# Power_Supply_TLVM13630.net
KiCad netlist of a schematic drawn in Altium Designer
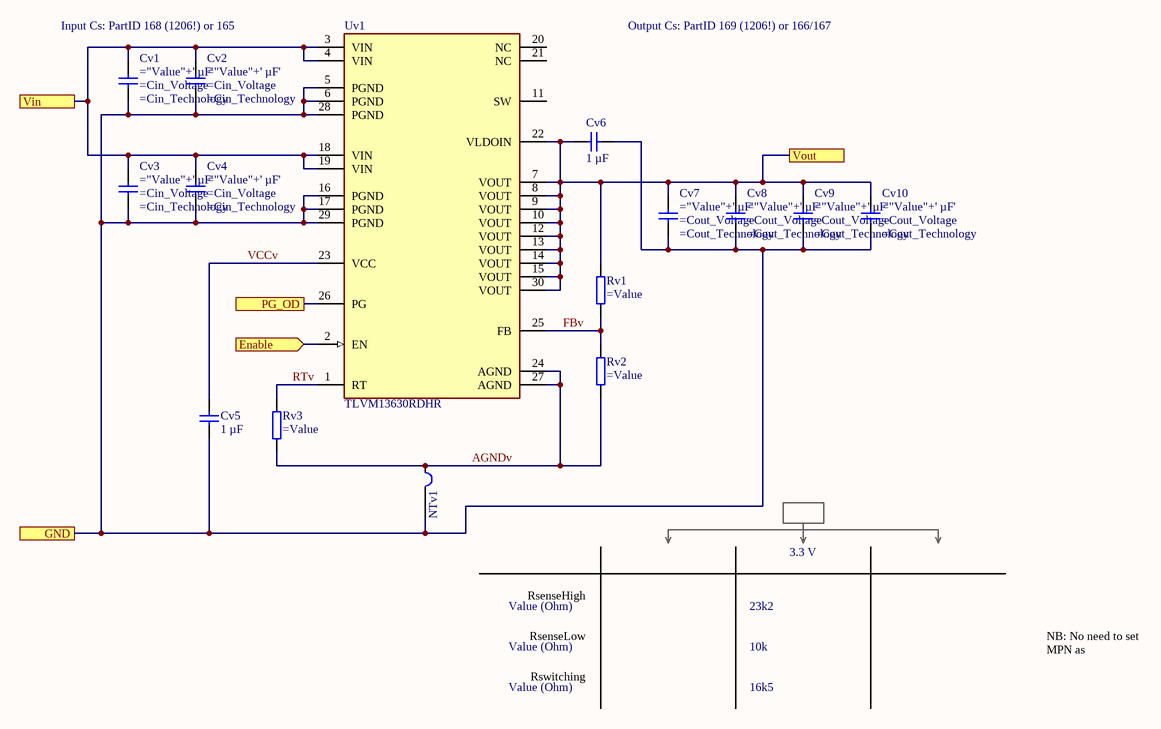
[diagram p0: Power_Supply_TLVM13630.SchDoc]

(export (version "E")
  (design (tool "Eeschema 10.0.6"))
  (components
    (comp (ref "Cv1")
      (value "µF")
      (footprint "C_1210_TE")
      (description "Generic capacitor (parametric)")
      (fields
        (field (name "MANUFACTURER PART NUMBER") "UZgen_C_1210_uF__")
        (field (name "MANUFACTURER") "UZgen")
        (field (name "CREATED FROM") "UZgenTool")
      )
      (libsource (lib "user") (part "CAP-NP"))
    )
    (comp (ref "Cv2")
      (value "µF")
      (footprint "C_1210_TE")
      (description "Generic capacitor (parametric)")
      (fields
        (field (name "MANUFACTURER PART NUMBER") "UZgen_C_1210_uF__")
        (field (name "MANUFACTURER") "UZgen")
        (field (name "CREATED FROM") "UZgenTool")
      )
      (libsource (lib "user") (part "CAP-NP"))
    )
    (comp (ref "Cv3")
      (value "µF")
      (footprint "C_1210_TE")
      (description "Generic capacitor (parametric)")
      (fields
        (field (name "MANUFACTURER PART NUMBER") "UZgen_C_1210_uF__")
        (field (name "MANUFACTURER") "UZgen")
        (field (name "CREATED FROM") "UZgenTool")
      )
      (libsource (lib "user") (part "CAP-NP"))
    )
    (comp (ref "Cv4")
      (value "µF")
      (footprint "C_1210_TE")
      (description "Generic capacitor (parametric)")
      (fields
        (field (name "MANUFACTURER PART NUMBER") "UZgen_C_1210_uF__")
        (field (name "MANUFACTURER") "UZgen")
        (field (name "CREATED FROM") "UZgenTool")
      )
      (libsource (lib "user") (part "CAP-NP"))
    )
    (comp (ref "Cv5")
      (value "1 µF")
      (footprint "C_0603_TE")
      (description "Generic capacitor")
      (fields
        (field (name "MANUFACTURER PART NUMBER") "UZgen_C_0603_1uF_16V_X7R")
        (field (name "MANUFACTURER") "UZgen")
        (field (name "CREATED FROM") "UZgenTool")
      )
      (libsource (lib "user") (part "CAP-NP"))
    )
    (comp (ref "Cv6")
      (value "1 µF")
      (footprint "C_0603_TE")
      (description "Generic capacitor")
      (fields
        (field (name "MANUFACTURER PART NUMBER") "UZgen_C_0603_1uF_16V_X7R")
        (field (name "MANUFACTURER") "UZgen")
        (field (name "CREATED FROM") "UZgenTool")
      )
      (libsource (lib "user") (part "CAP-NP"))
    )
    (comp (ref "Cv7")
      (value "µF")
      (footprint "C_1210_TE")
      (description "Generic capacitor (parametric)")
      (fields
        (field (name "MANUFACTURER PART NUMBER") "UZgen_C_1210_uF__")
        (field (name "MANUFACTURER") "UZgen")
        (field (name "CREATED FROM") "UZgenTool")
      )
      (libsource (lib "user") (part "CAP-NP"))
    )
    (comp (ref "Cv8")
      (value "µF")
      (footprint "C_1210_TE")
      (description "Generic capacitor (parametric)")
      (fields
        (field (name "MANUFACTURER PART NUMBER") "UZgen_C_1210_uF__")
        (field (name "MANUFACTURER") "UZgen")
        (field (name "CREATED FROM") "UZgenTool")
      )
      (libsource (lib "user") (part "CAP-NP"))
    )
    (comp (ref "Cv9")
      (value "µF")
      (footprint "C_1210_TE")
      (description "Generic capacitor (parametric)")
      (fields
        (field (name "MANUFACTURER PART NUMBER") "UZgen_C_1210_uF__")
        (field (name "MANUFACTURER") "UZgen")
        (field (name "CREATED FROM") "UZgenTool")
      )
      (libsource (lib "user") (part "CAP-NP"))
    )
    (comp (ref "Cv10")
      (value "µF")
      (footprint "C_1210_TE")
      (description "Generic capacitor (parametric)")
      (fields
        (field (name "MANUFACTURER PART NUMBER") "UZgen_C_1210_uF__")
        (field (name "MANUFACTURER") "UZgen")
        (field (name "CREATED FROM") "UZgenTool")
      )
      (libsource (lib "user") (part "CAP-NP"))
    )
    (comp (ref "NTv1")
      (value "Net Tie 1 to 1")
      (footprint "1_to_1_NetTie_0.1mm-NoOverlayPrint")
      (description "Net Tie 1 to 1. Joins two nets without producing a DRC error or renaming one of the nets")
      (fields (field (name "CREATED BY") "MGeier"))
      (libsource (lib "user") (part "NetTie_1_to_1_small"))
    )
    (comp (ref "Rv1")
      (value "~")
      (footprint "R_0603_TE")
      (description "Generic resistor (parametric)")
      (fields
        (field (name "TOLERANCE") "1 %")
        (field (name "MANUFACTURER PART NUMBER") "UZgen_R_0603_")
        (field (name "CREATED FROM") "UZgenTool")
      )
      (libsource (lib "user") (part "RES"))
    )
    (comp (ref "Rv2")
      (value "~")
      (footprint "R_0603_TE")
      (description "Generic resistor (parametric)")
      (fields
        (field (name "TOLERANCE") "1 %")
        (field (name "MANUFACTURER PART NUMBER") "UZgen_R_0603_")
        (field (name "CREATED FROM") "UZgenTool")
      )
      (libsource (lib "user") (part "RES"))
    )
    (comp (ref "Rv3")
      (value "~")
      (footprint "R_0603_TE")
      (description "Generic resistor (parametric)")
      (fields
        (field (name "MANUFACTURER PART NUMBER") "UZgen_R_0603_")
        (field (name "MANUFACTURER") "UZgen")
        (field (name "CREATED FROM") "UZgenTool")
      )
      (libsource (lib "user") (part "RES"))
    )
    (comp (ref "Uv1")
      (value "TLVM13630RDHR")
      (footprint "FP-RDH0030A-MFG_CUSTOMBOTSMETENTED")
      (description "3-V to 36-V Input, 1-V to 6-V Output, 3-A Power Module with integrated shielded inductor")
      (fields
        (field (name "MANUFACTURER") "Texas Instruments")
        (field (name "LCSC PART NUMBER") "C5219304")
        (field (name "CREATED FROM") "MGeier")
      )
      (libsource (lib "user") (part "TLVM136[23]0"))
    )
  )
  (nets
    (net (code "1") (name "/AGNDv") (class "Default")
      (node (ref "NTv1") (pin "1") (pinfunction "1_1") (pintype "passive"))
      (node (ref "Rv2") (pin "2") (pinfunction "2_2") (pintype "passive"))
      (node (ref "Rv3") (pin "2") (pinfunction "2_2") (pintype "passive"))
      (node (ref "Uv1") (pin "24") (pinfunction "AGND_24") (pintype "power_in"))
      (node (ref "Uv1") (pin "27") (pinfunction "AGND_27") (pintype "power_in"))
    )
    (net (code "2") (name "/Enable") (class "Default")
      (node (ref "Uv1") (pin "2") (pinfunction "EN_2") (pintype "input"))
    )
    (net (code "3") (name "/FBv") (class "Default")
      (node (ref "Rv1") (pin "2") (pinfunction "2_2") (pintype "passive"))
      (node (ref "Rv2") (pin "1") (pinfunction "1_1") (pintype "passive"))
      (node (ref "Uv1") (pin "25") (pinfunction "FB_25") (pintype "passive"))
    )
    (net (code "4") (name "/GND") (class "Default")
      (node (ref "Cv1") (pin "1") (pinfunction "1_1") (pintype "passive"))
      (node (ref "Cv10") (pin "1") (pinfunction "1_1") (pintype "passive"))
      (node (ref "Cv2") (pin "1") (pinfunction "1_1") (pintype "passive"))
      (node (ref "Cv3") (pin "1") (pinfunction "1_1") (pintype "passive"))
      (node (ref "Cv4") (pin "1") (pinfunction "1_1") (pintype "passive"))
      (node (ref "Cv5") (pin "1") (pinfunction "1_1") (pintype "passive"))
      (node (ref "Cv6") (pin "1") (pinfunction "1_1") (pintype "passive"))
      (node (ref "Cv7") (pin "1") (pinfunction "1_1") (pintype "passive"))
      (node (ref "Cv8") (pin "1") (pinfunction "1_1") (pintype "passive"))
      (node (ref "Cv9") (pin "1") (pinfunction "1_1") (pintype "passive"))
      (node (ref "NTv1") (pin "2") (pinfunction "2_2") (pintype "passive"))
      (node (ref "Uv1") (pin "16") (pinfunction "PGND_16") (pintype "power_in"))
      (node (ref "Uv1") (pin "17") (pinfunction "PGND_17") (pintype "power_in"))
      (node (ref "Uv1") (pin "28") (pinfunction "PGND_28") (pintype "power_in"))
      (node (ref "Uv1") (pin "29") (pinfunction "PGND_29") (pintype "power_in"))
      (node (ref "Uv1") (pin "5") (pinfunction "PGND_5") (pintype "power_in"))
      (node (ref "Uv1") (pin "6") (pinfunction "PGND_6") (pintype "power_in"))
    )
    (net (code "5") (name "/PG_OD") (class "Default")
      (node (ref "Uv1") (pin "26") (pinfunction "PG_26") (pintype "open_collector"))
    )
    (net (code "6") (name "/RTv") (class "Default")
      (node (ref "Rv3") (pin "1") (pinfunction "1_1") (pintype "passive"))
      (node (ref "Uv1") (pin "1") (pinfunction "RT_1") (pintype "passive"))
    )
    (net (code "7") (name "/VCCv") (class "Default")
      (node (ref "Cv5") (pin "2") (pinfunction "2_2") (pintype "passive"))
      (node (ref "Uv1") (pin "23") (pinfunction "VCC_23") (pintype "power_in"))
    )
    (net (code "8") (name "/Vin") (class "Default")
      (node (ref "Cv1") (pin "2") (pinfunction "2_2") (pintype "passive"))
      (node (ref "Cv2") (pin "2") (pinfunction "2_2") (pintype "passive"))
      (node (ref "Cv3") (pin "2") (pinfunction "2_2") (pintype "passive"))
      (node (ref "Cv4") (pin "2") (pinfunction "2_2") (pintype "passive"))
      (node (ref "Uv1") (pin "18") (pinfunction "VIN_18") (pintype "power_in"))
      (node (ref "Uv1") (pin "19") (pinfunction "VIN_19") (pintype "power_in"))
      (node (ref "Uv1") (pin "3") (pinfunction "VIN_3") (pintype "power_in"))
      (node (ref "Uv1") (pin "4") (pinfunction "VIN_4") (pintype "power_in"))
    )
    (net (code "9") (name "/Vout") (class "Default")
      (node (ref "Cv10") (pin "2") (pinfunction "2_2") (pintype "passive"))
      (node (ref "Cv6") (pin "2") (pinfunction "2_2") (pintype "passive"))
      (node (ref "Cv7") (pin "2") (pinfunction "2_2") (pintype "passive"))
      (node (ref "Cv8") (pin "2") (pinfunction "2_2") (pintype "passive"))
      (node (ref "Cv9") (pin "2") (pinfunction "2_2") (pintype "passive"))
      (node (ref "Rv1") (pin "1") (pinfunction "1_1") (pintype "passive"))
      (node (ref "Uv1") (pin "10") (pinfunction "VOUT_10") (pintype "power_in"))
      (node (ref "Uv1") (pin "12") (pinfunction "VOUT_12") (pintype "power_in"))
      (node (ref "Uv1") (pin "13") (pinfunction "VOUT_13") (pintype "power_in"))
      (node (ref "Uv1") (pin "14") (pinfunction "VOUT_14") (pintype "power_in"))
      (node (ref "Uv1") (pin "15") (pinfunction "VOUT_15") (pintype "power_in"))
      (node (ref "Uv1") (pin "22") (pinfunction "VLDOIN_22") (pintype "power_in"))
      (node (ref "Uv1") (pin "30") (pinfunction "VOUT_30") (pintype "power_in"))
      (node (ref "Uv1") (pin "7") (pinfunction "VOUT_7") (pintype "power_in"))
      (node (ref "Uv1") (pin "8") (pinfunction "VOUT_8") (pintype "power_in"))
      (node (ref "Uv1") (pin "9") (pinfunction "VOUT_9") (pintype "power_in"))
    )
    (net (code "10") (name "unconnected-(Uv1-NC-Pad20)") (class "Default")
      (node (ref "Uv1") (pin "20") (pinfunction "NC_20") (pintype "passive"))
    )
    (net (code "11") (name "unconnected-(Uv1-NC-Pad21)") (class "Default")
      (node (ref "Uv1") (pin "21") (pinfunction "NC_21") (pintype "passive"))
    )
    (net (code "12") (name "unconnected-(Uv1-SW-Pad11)") (class "Default")
      (node (ref "Uv1") (pin "11") (pinfunction "SW_11") (pintype "passive"))
    )
  )
)
